# DIO.net
KiCad netlist of a schematic drawn in Altium Designer
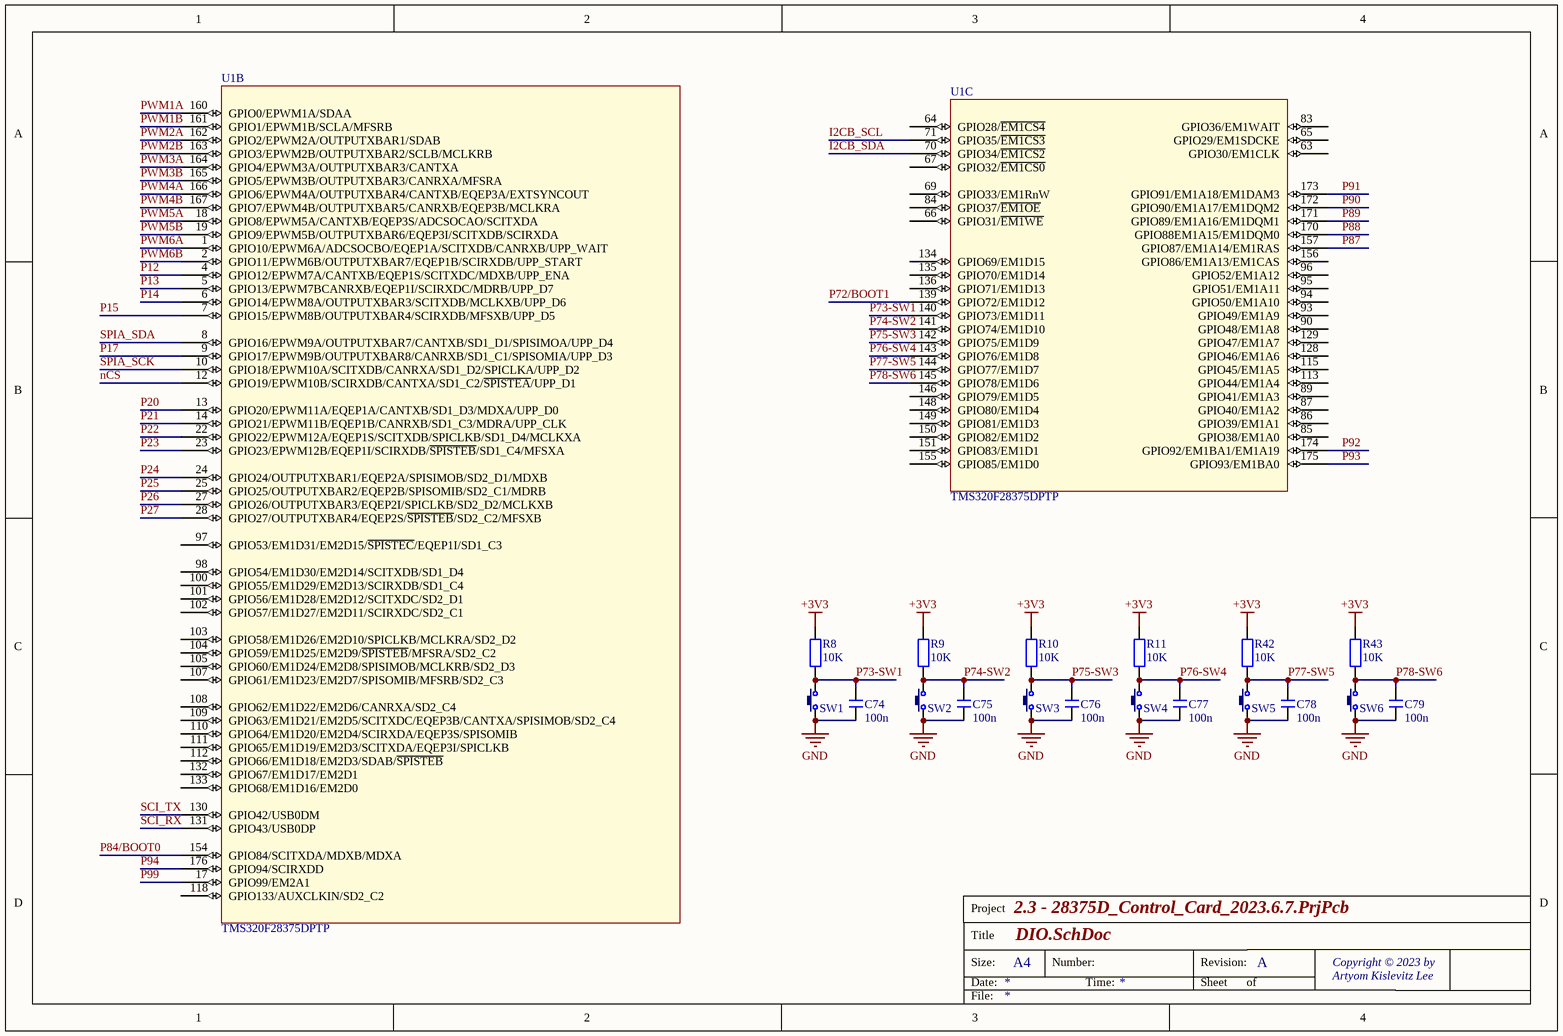
[diagram p0: DIO.SchDoc]

(export (version "E")
  (design (tool "Eeschema 10.0.6"))
  (components
    (comp (ref "C74")
      (value "100n")
      (footprint "C 0805_L")
      (description "贴片电容")
      (libsource (lib "01 - 电容-电阻-电感") (part "C"))
    )
    (comp (ref "C75")
      (value "100n")
      (footprint "C 0805_L")
      (description "贴片电容")
      (libsource (lib "01 - 电容-电阻-电感") (part "C"))
    )
    (comp (ref "C76")
      (value "100n")
      (footprint "C 0805_L")
      (description "贴片电容")
      (libsource (lib "01 - 电容-电阻-电感") (part "C"))
    )
    (comp (ref "C77")
      (value "100n")
      (footprint "C 0805_L")
      (description "贴片电容")
      (libsource (lib "01 - 电容-电阻-电感") (part "C"))
    )
    (comp (ref "C78")
      (value "100n")
      (footprint "C 0805_L")
      (description "贴片电容")
      (libsource (lib "01 - 电容-电阻-电感") (part "C"))
    )
    (comp (ref "C79")
      (value "100n")
      (footprint "C 0805_L")
      (description "贴片电容")
      (libsource (lib "01 - 电容-电阻-电感") (part "C"))
    )
    (comp (ref "R8")
      (value "10K")
      (footprint "R 0805_L")
      (description "贴片电阻")
      (libsource (lib "01 - 电容-电阻-电感") (part "R"))
    )
    (comp (ref "R9")
      (value "10K")
      (footprint "R 0805_L")
      (description "贴片电阻")
      (libsource (lib "01 - 电容-电阻-电感") (part "R"))
    )
    (comp (ref "R10")
      (value "10K")
      (footprint "R 0805_L")
      (description "贴片电阻")
      (libsource (lib "01 - 电容-电阻-电感") (part "R"))
    )
    (comp (ref "R11")
      (value "10K")
      (footprint "R 0805_L")
      (description "贴片电阻")
      (libsource (lib "01 - 电容-电阻-电感") (part "R"))
    )
    (comp (ref "R42")
      (value "10K")
      (footprint "R 0805_L")
      (description "贴片电阻")
      (libsource (lib "01 - 电容-电阻-电感") (part "R"))
    )
    (comp (ref "R43")
      (value "10K")
      (footprint "R 0805_L")
      (description "贴片电阻")
      (libsource (lib "01 - 电容-电阻-电感") (part "R"))
    )
    (comp (ref "SW1")
      (value "3x6x5")
      (footprint "TSW DIP-3*6*4.3")
      (description "3x6轻触开关")
      (libsource (lib "03 - 按键-开关-晶振-蜂鸣器") (part "TSW 3x6"))
    )
    (comp (ref "SW2")
      (value "3x6x5")
      (footprint "TSW DIP-3*6*4.3")
      (description "3x6轻触开关")
      (libsource (lib "03 - 按键-开关-晶振-蜂鸣器") (part "TSW 3x6"))
    )
    (comp (ref "SW3")
      (value "3x6x5")
      (footprint "TSW DIP-3*6*4.3")
      (description "3x6轻触开关")
      (libsource (lib "03 - 按键-开关-晶振-蜂鸣器") (part "TSW 3x6"))
    )
    (comp (ref "SW4")
      (value "3x6x5")
      (footprint "TSW DIP-3*6*4.3")
      (description "3x6轻触开关")
      (libsource (lib "03 - 按键-开关-晶振-蜂鸣器") (part "TSW 3x6"))
    )
    (comp (ref "SW5")
      (value "3x6x5")
      (footprint "TSW DIP-3*6*4.3")
      (description "3x6轻触开关")
      (libsource (lib "03 - 按键-开关-晶振-蜂鸣器") (part "TSW 3x6"))
    )
    (comp (ref "SW6")
      (value "3x6x5")
      (footprint "TSW DIP-3*6*4.3")
      (description "3x6轻触开关")
      (libsource (lib "03 - 按键-开关-晶振-蜂鸣器") (part "TSW 3x6"))
    )
    (comp (ref "U1")
      (value "TMS320F28375DPTP")
      (footprint "LQFP176-E 24x24_N")
      (description "DSP 176")
      (fields
        (field (name "PARTNUMBER") "TMS320F28377DPTP")
        (field (name "MANUFACTURER") "Texas Instruments")
      )
      (libsource (lib "39 - 其他芯片类") (part "TMS320F28377DPTP"))
    )
  )
  (nets
    (net (code "1") (name "+3V3") (class "Default")
      (node (ref "R10") (pin "2") (pinfunction "2_2") (pintype "passive"))
      (node (ref "R11") (pin "2") (pinfunction "2_2") (pintype "passive"))
      (node (ref "R42") (pin "2") (pinfunction "2_2") (pintype "passive"))
      (node (ref "R43") (pin "2") (pinfunction "2_2") (pintype "passive"))
      (node (ref "R8") (pin "2") (pinfunction "2_2") (pintype "passive"))
      (node (ref "R9") (pin "2") (pinfunction "2_2") (pintype "passive"))
    )
    (net (code "2") (name "/I2CB_SCL") (class "Default")
      (node (ref "U1") (pin "71") (pinfunction "GPIO35/~{EM1CS3}_71") (pintype "bidirectional"))
    )
    (net (code "3") (name "/I2CB_SDA") (class "Default")
      (node (ref "U1") (pin "70") (pinfunction "GPIO34/~{EM1CS2}_70") (pintype "bidirectional"))
    )
    (net (code "4") (name "/P12") (class "Default")
      (node (ref "U1") (pin "4") (pinfunction "GPIO12/EPWM7A/CANTXB/EQEP1S/SCITXDC/MDXB/UPP_ENA_4") (pintype "bidirectional"))
    )
    (net (code "5") (name "/P13") (class "Default")
      (node (ref "U1") (pin "5") (pinfunction "GPIO13/EPWM7BCANRXB/EQEP1I/SCIRXDC/MDRB/UPP_D7_5") (pintype "bidirectional"))
    )
    (net (code "6") (name "/P14") (class "Default")
      (node (ref "U1") (pin "6") (pinfunction "GPIO14/EPWM8A/OUTPUTXBAR3/SCITXDB/MCLKXB/UPP_D6_6") (pintype "bidirectional"))
    )
    (net (code "7") (name "/P15") (class "Default")
      (node (ref "U1") (pin "7") (pinfunction "GPIO15/EPWM8B/OUTPUTXBAR4/SCIRXDB/MFSXB/UPP_D5_7") (pintype "bidirectional"))
    )
    (net (code "8") (name "/P17") (class "Default")
      (node (ref "U1") (pin "9") (pinfunction "GPIO17/EPWM9B/OUTPUTXBAR8/CANRXB/SD1_C1/SPISOMIA/UPP_D3_9") (pintype "bidirectional"))
    )
    (net (code "9") (name "/P20") (class "Default")
      (node (ref "U1") (pin "13") (pinfunction "GPIO20/EPWM11A/EQEP1A/CANTXB/SD1_D3/MDXA/UPP_D0_13") (pintype "bidirectional"))
    )
    (net (code "10") (name "/P21") (class "Default")
      (node (ref "U1") (pin "14") (pinfunction "GPIO21/EPWM11B/EQEP1B/CANRXB/SD1_C3/MDRA/UPP_CLK_14") (pintype "bidirectional"))
    )
    (net (code "11") (name "/P22") (class "Default")
      (node (ref "U1") (pin "22") (pinfunction "GPIO22/EPWM12A/EQEP1S/SCITXDB/SPICLKB/SD1_D4/MCLKXA_22") (pintype "bidirectional"))
    )
    (net (code "12") (name "/P23") (class "Default")
      (node (ref "U1") (pin "23") (pinfunction "GPIO23/EPWM12B/EQEP1I/SCIRXDB/~{SPISTEB}/SD1_C4/MFSXA_23") (pintype "bidirectional"))
    )
    (net (code "13") (name "/P24") (class "Default")
      (node (ref "U1") (pin "24") (pinfunction "GPIO24/OUTPUTXBAR1/EQEP2A/SPISIMOB/SD2_D1/MDXB_24") (pintype "bidirectional"))
    )
    (net (code "14") (name "/P25") (class "Default")
      (node (ref "U1") (pin "25") (pinfunction "GPIO25/OUTPUTXBAR2/EQEP2B/SPISOMIB/SD2_C1/MDRB_25") (pintype "bidirectional"))
    )
    (net (code "15") (name "/P26") (class "Default")
      (node (ref "U1") (pin "27") (pinfunction "GPIO26/OUTPUTXBAR3/EQEP2I/SPICLKB/SD2_D2/MCLKXB_27") (pintype "bidirectional"))
    )
    (net (code "16") (name "/P27") (class "Default")
      (node (ref "U1") (pin "28") (pinfunction "GPIO27/OUTPUTXBAR4/EQEP2S/~{SPISTEB}/SD2_C2/MFSXB_28") (pintype "bidirectional"))
    )
    (net (code "17") (name "/P72{slash}BOOT1") (class "Default")
      (node (ref "U1") (pin "139") (pinfunction "GPIO72/EM1D12_139") (pintype "bidirectional"))
    )
    (net (code "18") (name "/P73-SW1") (class "Default")
      (node (ref "C74") (pin "2") (pinfunction "2_2") (pintype "passive"))
      (node (ref "R8") (pin "1") (pinfunction "1_1") (pintype "passive"))
      (node (ref "SW1") (pin "2") (pinfunction "2_2") (pintype "passive"))
      (node (ref "U1") (pin "140") (pinfunction "GPIO73/EM1D11_140") (pintype "bidirectional"))
    )
    (net (code "19") (name "/P74-SW2") (class "Default")
      (node (ref "C75") (pin "2") (pinfunction "2_2") (pintype "passive"))
      (node (ref "R9") (pin "1") (pinfunction "1_1") (pintype "passive"))
      (node (ref "SW2") (pin "2") (pinfunction "2_2") (pintype "passive"))
      (node (ref "U1") (pin "141") (pinfunction "GPIO74/EM1D10_141") (pintype "bidirectional"))
    )
    (net (code "20") (name "/P75-SW3") (class "Default")
      (node (ref "C76") (pin "2") (pinfunction "2_2") (pintype "passive"))
      (node (ref "R10") (pin "1") (pinfunction "1_1") (pintype "passive"))
      (node (ref "SW3") (pin "2") (pinfunction "2_2") (pintype "passive"))
      (node (ref "U1") (pin "142") (pinfunction "GPIO75/EM1D9_142") (pintype "bidirectional"))
    )
    (net (code "21") (name "/P76-SW4") (class "Default")
      (node (ref "C77") (pin "2") (pinfunction "2_2") (pintype "passive"))
      (node (ref "R11") (pin "1") (pinfunction "1_1") (pintype "passive"))
      (node (ref "SW4") (pin "2") (pinfunction "2_2") (pintype "passive"))
      (node (ref "U1") (pin "143") (pinfunction "GPIO76/EM1D8_143") (pintype "bidirectional"))
    )
    (net (code "22") (name "/P77-SW5") (class "Default")
      (node (ref "C78") (pin "2") (pinfunction "2_2") (pintype "passive"))
      (node (ref "R42") (pin "1") (pinfunction "1_1") (pintype "passive"))
      (node (ref "SW5") (pin "2") (pinfunction "2_2") (pintype "passive"))
      (node (ref "U1") (pin "144") (pinfunction "GPIO77/EM1D7_144") (pintype "bidirectional"))
    )
    (net (code "23") (name "/P78-SW6") (class "Default")
      (node (ref "C79") (pin "2") (pinfunction "2_2") (pintype "passive"))
      (node (ref "R43") (pin "1") (pinfunction "1_1") (pintype "passive"))
      (node (ref "SW6") (pin "2") (pinfunction "2_2") (pintype "passive"))
      (node (ref "U1") (pin "145") (pinfunction "GPIO78/EM1D6_145") (pintype "bidirectional"))
    )
    (net (code "24") (name "/P84{slash}BOOT0") (class "Default")
      (node (ref "U1") (pin "154") (pinfunction "GPIO84/SCITXDA/MDXB/MDXA_154") (pintype "bidirectional"))
    )
    (net (code "25") (name "/P87") (class "Default")
      (node (ref "U1") (pin "157") (pinfunction "GPIO87/EM1A14/EM1RAS_157") (pintype "bidirectional"))
    )
    (net (code "26") (name "/P88") (class "Default")
      (node (ref "U1") (pin "170") (pinfunction "GPIO88EM1A15/EM1DQM0_170") (pintype "bidirectional"))
    )
    (net (code "27") (name "/P89") (class "Default")
      (node (ref "U1") (pin "171") (pinfunction "GPIO89/EM1A16/EM1DQM1_171") (pintype "bidirectional"))
    )
    (net (code "28") (name "/P90") (class "Default")
      (node (ref "U1") (pin "172") (pinfunction "GPIO90/EM1A17/EM1DQM2_172") (pintype "bidirectional"))
    )
    (net (code "29") (name "/P91") (class "Default")
      (node (ref "U1") (pin "173") (pinfunction "GPIO91/EM1A18/EM1DAM3_173") (pintype "bidirectional"))
    )
    (net (code "30") (name "/P92") (class "Default")
      (node (ref "U1") (pin "174") (pinfunction "GPIO92/EM1BA1/EM1A19_174") (pintype "bidirectional"))
    )
    (net (code "31") (name "/P93") (class "Default")
      (node (ref "U1") (pin "175") (pinfunction "GPIO93/EM1BA0_175") (pintype "bidirectional"))
    )
    (net (code "32") (name "/P94") (class "Default")
      (node (ref "U1") (pin "176") (pinfunction "GPIO94/SCIRXDD_176") (pintype "bidirectional"))
    )
    (net (code "33") (name "/P99") (class "Default")
      (node (ref "U1") (pin "17") (pinfunction "GPIO99/EM2A1_17") (pintype "bidirectional"))
    )
    (net (code "34") (name "/PWM1A") (class "Default")
      (node (ref "U1") (pin "160") (pinfunction "GPIO0/EPWM1A/SDAA_160") (pintype "bidirectional"))
    )
    (net (code "35") (name "/PWM1B") (class "Default")
      (node (ref "U1") (pin "161") (pinfunction "GPIO1/EPWM1B/SCLA/MFSRB_161") (pintype "bidirectional"))
    )
    (net (code "36") (name "/PWM2A") (class "Default")
      (node (ref "U1") (pin "162") (pinfunction "GPIO2/EPWM2A/OUTPUTXBAR1/SDAB_162") (pintype "bidirectional"))
    )
    (net (code "37") (name "/PWM2B") (class "Default")
      (node (ref "U1") (pin "163") (pinfunction "GPIO3/EPWM2B/OUTPUTXBAR2/SCLB/MCLKRB_163") (pintype "bidirectional"))
    )
    (net (code "38") (name "/PWM3A") (class "Default")
      (node (ref "U1") (pin "164") (pinfunction "GPIO4/EPWM3A/OUTPUTXBAR3/CANTXA_164") (pintype "bidirectional"))
    )
    (net (code "39") (name "/PWM3B") (class "Default")
      (node (ref "U1") (pin "165") (pinfunction "GPIO5/EPWM3B/OUTPUTXBAR3/CANRXA/MFSRA_165") (pintype "bidirectional"))
    )
    (net (code "40") (name "/PWM4A") (class "Default")
      (node (ref "U1") (pin "166") (pinfunction "GPIO6/EPWM4A/OUTPUTXBAR4/CANTXB/EQEP3A/EXTSYNCOUT_166") (pintype "bidirectional"))
    )
    (net (code "41") (name "/PWM4B") (class "Default")
      (node (ref "U1") (pin "167") (pinfunction "GPIO7/EPWM4B/OUTPUTXBAR5/CANRXB/EQEP3B/MCLKRA_167") (pintype "bidirectional"))
    )
    (net (code "42") (name "/PWM5A") (class "Default")
      (node (ref "U1") (pin "18") (pinfunction "GPIO8/EPWM5A/CANTXB/EQEP3S/ADCSOCAO/SCITXDA_18") (pintype "bidirectional"))
    )
    (net (code "43") (name "/PWM5B") (class "Default")
      (node (ref "U1") (pin "19") (pinfunction "GPIO9/EPWM5B/OUTPUTXBAR6/EQEP3I/SCITXDB/SCIRXDA_19") (pintype "bidirectional"))
    )
    (net (code "44") (name "/PWM6A") (class "Default")
      (node (ref "U1") (pin "1") (pinfunction "GPIO10/EPWM6A/ADCSOCBO/EQEP1A/SCITXDB/CANRXB/UPP_WAIT_1") (pintype "bidirectional"))
    )
    (net (code "45") (name "/PWM6B") (class "Default")
      (node (ref "U1") (pin "2") (pinfunction "GPIO11/EPWM6B/OUTPUTXBAR7/EQEP1B/SCIRXDB/UPP_START_2") (pintype "bidirectional"))
    )
    (net (code "46") (name "/SCI_RX") (class "Default")
      (node (ref "U1") (pin "131") (pinfunction "GPIO43/USB0DP_131") (pintype "bidirectional"))
    )
    (net (code "47") (name "/SCI_TX") (class "Default")
      (node (ref "U1") (pin "130") (pinfunction "GPIO42/USB0DM_130") (pintype "bidirectional"))
    )
    (net (code "48") (name "/SPIA_SCK") (class "Default")
      (node (ref "U1") (pin "10") (pinfunction "GPIO18/EPWM10A/SCITXDB/CANRXA/SD1_D2/SPICLKA/UPP_D2_10") (pintype "bidirectional"))
    )
    (net (code "49") (name "/SPIA_SDA") (class "Default")
      (node (ref "U1") (pin "8") (pinfunction "GPIO16/EPWM9A/OUTPUTXBAR7/CANTXB/SD1_D1/SPISIMOA/UPP_D4_8") (pintype "bidirectional"))
    )
    (net (code "50") (name "/nCS") (class "Default")
      (node (ref "U1") (pin "12") (pinfunction "GPIO19/EPWM10B/SCIRXDB/CANTXA/SD1_C2/~{SPISTEA}/UPP_D1_12") (pintype "bidirectional"))
    )
    (net (code "51") (name "GND") (class "Default")
      (node (ref "C74") (pin "1") (pinfunction "1_1") (pintype "passive"))
      (node (ref "C75") (pin "1") (pinfunction "1_1") (pintype "passive"))
      (node (ref "C76") (pin "1") (pinfunction "1_1") (pintype "passive"))
      (node (ref "C77") (pin "1") (pinfunction "1_1") (pintype "passive"))
      (node (ref "C78") (pin "1") (pinfunction "1_1") (pintype "passive"))
      (node (ref "C79") (pin "1") (pinfunction "1_1") (pintype "passive"))
      (node (ref "SW1") (pin "1") (pinfunction "1_1") (pintype "passive"))
      (node (ref "SW2") (pin "1") (pinfunction "1_1") (pintype "passive"))
      (node (ref "SW3") (pin "1") (pinfunction "1_1") (pintype "passive"))
      (node (ref "SW4") (pin "1") (pinfunction "1_1") (pintype "passive"))
      (node (ref "SW5") (pin "1") (pinfunction "1_1") (pintype "passive"))
      (node (ref "SW6") (pin "1") (pinfunction "1_1") (pintype "passive"))
    )
    (net (code "52") (name "unconnected-(U1B-GPIO53{slash}EM1D31{slash}EM2D15{slash}~{SPISTEC}{slash}EQEP1I{slash}SD1_C3-Pad97)") (class "Default")
      (node (ref "U1") (pin "97") (pinfunction "GPIO53/EM1D31/EM2D15/~{SPISTEC}/EQEP1I/SD1_C3_97") (pintype "bidirectional"))
    )
    (net (code "53") (name "unconnected-(U1B-GPIO54{slash}EM1D30{slash}EM2D14{slash}SCITXDB{slash}SD1_D4-Pad98)") (class "Default")
      (node (ref "U1") (pin "98") (pinfunction "GPIO54/EM1D30/EM2D14/SCITXDB/SD1_D4_98") (pintype "bidirectional"))
    )
    (net (code "54") (name "unconnected-(U1B-GPIO55{slash}EM1D29{slash}EM2D13{slash}SCIRXDB{slash}SD1_C4-Pad100)") (class "Default")
      (node (ref "U1") (pin "100") (pinfunction "GPIO55/EM1D29/EM2D13/SCIRXDB/SD1_C4_100") (pintype "bidirectional"))
    )
    (net (code "55") (name "unconnected-(U1B-GPIO56{slash}EM1D28{slash}EM2D12{slash}SCITXDC{slash}SD2_D1-Pad101)") (class "Default")
      (node (ref "U1") (pin "101") (pinfunction "GPIO56/EM1D28/EM2D12/SCITXDC/SD2_D1_101") (pintype "bidirectional"))
    )
    (net (code "56") (name "unconnected-(U1B-GPIO57{slash}EM1D27{slash}EM2D11{slash}SCIRXDC{slash}SD2_C1-Pad102)") (class "Default")
      (node (ref "U1") (pin "102") (pinfunction "GPIO57/EM1D27/EM2D11/SCIRXDC/SD2_C1_102") (pintype "bidirectional"))
    )
    (net (code "57") (name "unconnected-(U1B-GPIO58{slash}EM1D26{slash}EM2D10{slash}SPICLKB{slash}MCLKRA{slash}SD2_D2-Pad103)") (class "Default")
      (node (ref "U1") (pin "103") (pinfunction "GPIO58/EM1D26/EM2D10/SPICLKB/MCLKRA/SD2_D2_103") (pintype "bidirectional"))
    )
    (net (code "58") (name "unconnected-(U1B-GPIO59{slash}EM1D25{slash}EM2D9{slash}~{SPISTEB}{slash}MFSRA{slash}SD2_C2-Pad104)") (class "Default")
      (node (ref "U1") (pin "104") (pinfunction "GPIO59/EM1D25/EM2D9/~{SPISTEB}/MFSRA/SD2_C2_104") (pintype "bidirectional"))
    )
    (net (code "59") (name "unconnected-(U1B-GPIO60{slash}EM1D24{slash}EM2D8{slash}SPISIMOB{slash}MCLKRB{slash}SD2_D3-Pad105)") (class "Default")
      (node (ref "U1") (pin "105") (pinfunction "GPIO60/EM1D24/EM2D8/SPISIMOB/MCLKRB/SD2_D3_105") (pintype "bidirectional"))
    )
    (net (code "60") (name "unconnected-(U1B-GPIO61{slash}EM1D23{slash}EM2D7{slash}SPISOMIB{slash}MFSRB{slash}SD2_C3-Pad107)") (class "Default")
      (node (ref "U1") (pin "107") (pinfunction "GPIO61/EM1D23/EM2D7/SPISOMIB/MFSRB/SD2_C3_107") (pintype "bidirectional"))
    )
    (net (code "61") (name "unconnected-(U1B-GPIO62{slash}EM1D22{slash}EM2D6{slash}CANRXA{slash}SD2_C4-Pad108)") (class "Default")
      (node (ref "U1") (pin "108") (pinfunction "GPIO62/EM1D22/EM2D6/CANRXA/SD2_C4_108") (pintype "bidirectional"))
    )
    (net (code "62") (name "unconnected-(U1B-GPIO63{slash}EM1D21{slash}EM2D5{slash}SCITXDC{slash}EQEP3B{slash}CANTXA{slash}SPISIMOB{slash}SD2_C4-Pad109)") (class "Default")
      (node (ref "U1") (pin "109") (pinfunction "GPIO63/EM1D21/EM2D5/SCITXDC/EQEP3B/CANTXA/SPISIMOB/SD2_C4_109") (pintype "bidirectional"))
    )
    (net (code "63") (name "unconnected-(U1B-GPIO64{slash}EM1D20{slash}EM2D4{slash}SCIRXDA{slash}EQEP3S{slash}SPISOMIB-Pad110)") (class "Default")
      (node (ref "U1") (pin "110") (pinfunction "GPIO64/EM1D20/EM2D4/SCIRXDA/EQEP3S/SPISOMIB_110") (pintype "bidirectional"))
    )
    (net (code "64") (name "unconnected-(U1B-GPIO65{slash}EM1D19{slash}EM2D3{slash}SCITXDA{slash}EQEP3I{slash}SPICLKB-Pad111)") (class "Default")
      (node (ref "U1") (pin "111") (pinfunction "GPIO65/EM1D19/EM2D3/SCITXDA/EQEP3I/SPICLKB_111") (pintype "bidirectional"))
    )
    (net (code "65") (name "unconnected-(U1B-GPIO66{slash}EM1D18{slash}EM2D3{slash}SDAB{slash}~{SPISTEB}-Pad112)") (class "Default")
      (node (ref "U1") (pin "112") (pinfunction "GPIO66/EM1D18/EM2D3/SDAB/~{SPISTEB}_112") (pintype "bidirectional"))
    )
    (net (code "66") (name "unconnected-(U1B-GPIO67{slash}EM1D17{slash}EM2D1-Pad132)") (class "Default")
      (node (ref "U1") (pin "132") (pinfunction "GPIO67/EM1D17/EM2D1_132") (pintype "bidirectional"))
    )
    (net (code "67") (name "unconnected-(U1B-GPIO68{slash}EM1D16{slash}EM2D0-Pad133)") (class "Default")
      (node (ref "U1") (pin "133") (pinfunction "GPIO68/EM1D16/EM2D0_133") (pintype "bidirectional"))
    )
    (net (code "68") (name "unconnected-(U1B-GPIO133{slash}AUXCLKIN{slash}SD2_C2-Pad118)") (class "Default")
      (node (ref "U1") (pin "118") (pinfunction "GPIO133/AUXCLKIN/SD2_C2_118") (pintype "bidirectional"))
    )
    (net (code "69") (name "unconnected-(U1C-GPIO28{slash}~{EM1CS4}-Pad64)") (class "Default")
      (node (ref "U1") (pin "64") (pinfunction "GPIO28/~{EM1CS4}_64") (pintype "bidirectional"))
    )
    (net (code "70") (name "unconnected-(U1C-GPIO29{slash}EM1SDCKE-Pad65)") (class "Default")
      (node (ref "U1") (pin "65") (pinfunction "GPIO29/EM1SDCKE_65") (pintype "bidirectional"))
    )
    (net (code "71") (name "unconnected-(U1C-GPIO30{slash}EM1CLK-Pad63)") (class "Default")
      (node (ref "U1") (pin "63") (pinfunction "GPIO30/EM1CLK_63") (pintype "bidirectional"))
    )
    (net (code "72") (name "unconnected-(U1C-GPIO31{slash}~{EM1WE}-Pad66)") (class "Default")
      (node (ref "U1") (pin "66") (pinfunction "GPIO31/~{EM1WE}_66") (pintype "bidirectional"))
    )
    (net (code "73") (name "unconnected-(U1C-GPIO32{slash}~{EM1CS0}-Pad67)") (class "Default")
      (node (ref "U1") (pin "67") (pinfunction "GPIO32/~{EM1CS0}_67") (pintype "bidirectional"))
    )
    (net (code "74") (name "unconnected-(U1C-GPIO33{slash}EM1RnW-Pad69)") (class "Default")
      (node (ref "U1") (pin "69") (pinfunction "GPIO33/EM1RnW_69") (pintype "bidirectional"))
    )
    (net (code "75") (name "unconnected-(U1C-GPIO36{slash}EM1WAIT-Pad83)") (class "Default")
      (node (ref "U1") (pin "83") (pinfunction "GPIO36/EM1WAIT_83") (pintype "bidirectional"))
    )
    (net (code "76") (name "unconnected-(U1C-GPIO37{slash}~{EM1OE}-Pad84)") (class "Default")
      (node (ref "U1") (pin "84") (pinfunction "GPIO37/~{EM1OE}_84") (pintype "bidirectional"))
    )
    (net (code "77") (name "unconnected-(U1C-GPIO38{slash}EM1A0-Pad85)") (class "Default")
      (node (ref "U1") (pin "85") (pinfunction "GPIO38/EM1A0_85") (pintype "bidirectional"))
    )
    (net (code "78") (name "unconnected-(U1C-GPIO39{slash}EM1A1-Pad86)") (class "Default")
      (node (ref "U1") (pin "86") (pinfunction "GPIO39/EM1A1_86") (pintype "bidirectional"))
    )
    (net (code "79") (name "unconnected-(U1C-GPIO40{slash}EM1A2-Pad87)") (class "Default")
      (node (ref "U1") (pin "87") (pinfunction "GPIO40/EM1A2_87") (pintype "bidirectional"))
    )
    (net (code "80") (name "unconnected-(U1C-GPIO41{slash}EM1A3-Pad89)") (class "Default")
      (node (ref "U1") (pin "89") (pinfunction "GPIO41/EM1A3_89") (pintype "bidirectional"))
    )
    (net (code "81") (name "unconnected-(U1C-GPIO44{slash}EM1A4-Pad113)") (class "Default")
      (node (ref "U1") (pin "113") (pinfunction "GPIO44/EM1A4_113") (pintype "bidirectional"))
    )
    (net (code "82") (name "unconnected-(U1C-GPIO45{slash}EM1A5-Pad115)") (class "Default")
      (node (ref "U1") (pin "115") (pinfunction "GPIO45/EM1A5_115") (pintype "bidirectional"))
    )
    (net (code "83") (name "unconnected-(U1C-GPIO46{slash}EM1A6-Pad128)") (class "Default")
      (node (ref "U1") (pin "128") (pinfunction "GPIO46/EM1A6_128") (pintype "bidirectional"))
    )
    (net (code "84") (name "unconnected-(U1C-GPIO47{slash}EM1A7-Pad129)") (class "Default")
      (node (ref "U1") (pin "129") (pinfunction "GPIO47/EM1A7_129") (pintype "bidirectional"))
    )
    (net (code "85") (name "unconnected-(U1C-GPIO48{slash}EM1A8-Pad90)") (class "Default")
      (node (ref "U1") (pin "90") (pinfunction "GPIO48/EM1A8_90") (pintype "bidirectional"))
    )
    (net (code "86") (name "unconnected-(U1C-GPIO49{slash}EM1A9-Pad93)") (class "Default")
      (node (ref "U1") (pin "93") (pinfunction "GPIO49/EM1A9_93") (pintype "bidirectional"))
    )
    (net (code "87") (name "unconnected-(U1C-GPIO50{slash}EM1A10-Pad94)") (class "Default")
      (node (ref "U1") (pin "94") (pinfunction "GPIO50/EM1A10_94") (pintype "bidirectional"))
    )
    (net (code "88") (name "unconnected-(U1C-GPIO51{slash}EM1A11-Pad95)") (class "Default")
      (node (ref "U1") (pin "95") (pinfunction "GPIO51/EM1A11_95") (pintype "bidirectional"))
    )
    (net (code "89") (name "unconnected-(U1C-GPIO52{slash}EM1A12-Pad96)") (class "Default")
      (node (ref "U1") (pin "96") (pinfunction "GPIO52/EM1A12_96") (pintype "bidirectional"))
    )
    (net (code "90") (name "unconnected-(U1C-GPIO69{slash}EM1D15-Pad134)") (class "Default")
      (node (ref "U1") (pin "134") (pinfunction "GPIO69/EM1D15_134") (pintype "bidirectional"))
    )
    (net (code "91") (name "unconnected-(U1C-GPIO70{slash}EM1D14-Pad135)") (class "Default")
      (node (ref "U1") (pin "135") (pinfunction "GPIO70/EM1D14_135") (pintype "bidirectional"))
    )
    (net (code "92") (name "unconnected-(U1C-GPIO71{slash}EM1D13-Pad136)") (class "Default")
      (node (ref "U1") (pin "136") (pinfunction "GPIO71/EM1D13_136") (pintype "bidirectional"))
    )
    (net (code "93") (name "unconnected-(U1C-GPIO79{slash}EM1D5-Pad146)") (class "Default")
      (node (ref "U1") (pin "146") (pinfunction "GPIO79/EM1D5_146") (pintype "bidirectional"))
    )
    (net (code "94") (name "unconnected-(U1C-GPIO80{slash}EM1D4-Pad148)") (class "Default")
      (node (ref "U1") (pin "148") (pinfunction "GPIO80/EM1D4_148") (pintype "bidirectional"))
    )
    (net (code "95") (name "unconnected-(U1C-GPIO81{slash}EM1D3-Pad149)") (class "Default")
      (node (ref "U1") (pin "149") (pinfunction "GPIO81/EM1D3_149") (pintype "bidirectional"))
    )
    (net (code "96") (name "unconnected-(U1C-GPIO82{slash}EM1D2-Pad150)") (class "Default")
      (node (ref "U1") (pin "150") (pinfunction "GPIO82/EM1D2_150") (pintype "bidirectional"))
    )
    (net (code "97") (name "unconnected-(U1C-GPIO83{slash}EM1D1-Pad151)") (class "Default")
      (node (ref "U1") (pin "151") (pinfunction "GPIO83/EM1D1_151") (pintype "bidirectional"))
    )
    (net (code "98") (name "unconnected-(U1C-GPIO85{slash}EM1D0-Pad155)") (class "Default")
      (node (ref "U1") (pin "155") (pinfunction "GPIO85/EM1D0_155") (pintype "bidirectional"))
    )
    (net (code "99") (name "unconnected-(U1C-GPIO86{slash}EM1A13{slash}EM1CAS-Pad156)") (class "Default")
      (node (ref "U1") (pin "156") (pinfunction "GPIO86/EM1A13/EM1CAS_156") (pintype "bidirectional"))
    )
  )
)
